# gleis-a-2.net
KiCad netlist of a schematic drawn in EAGLE
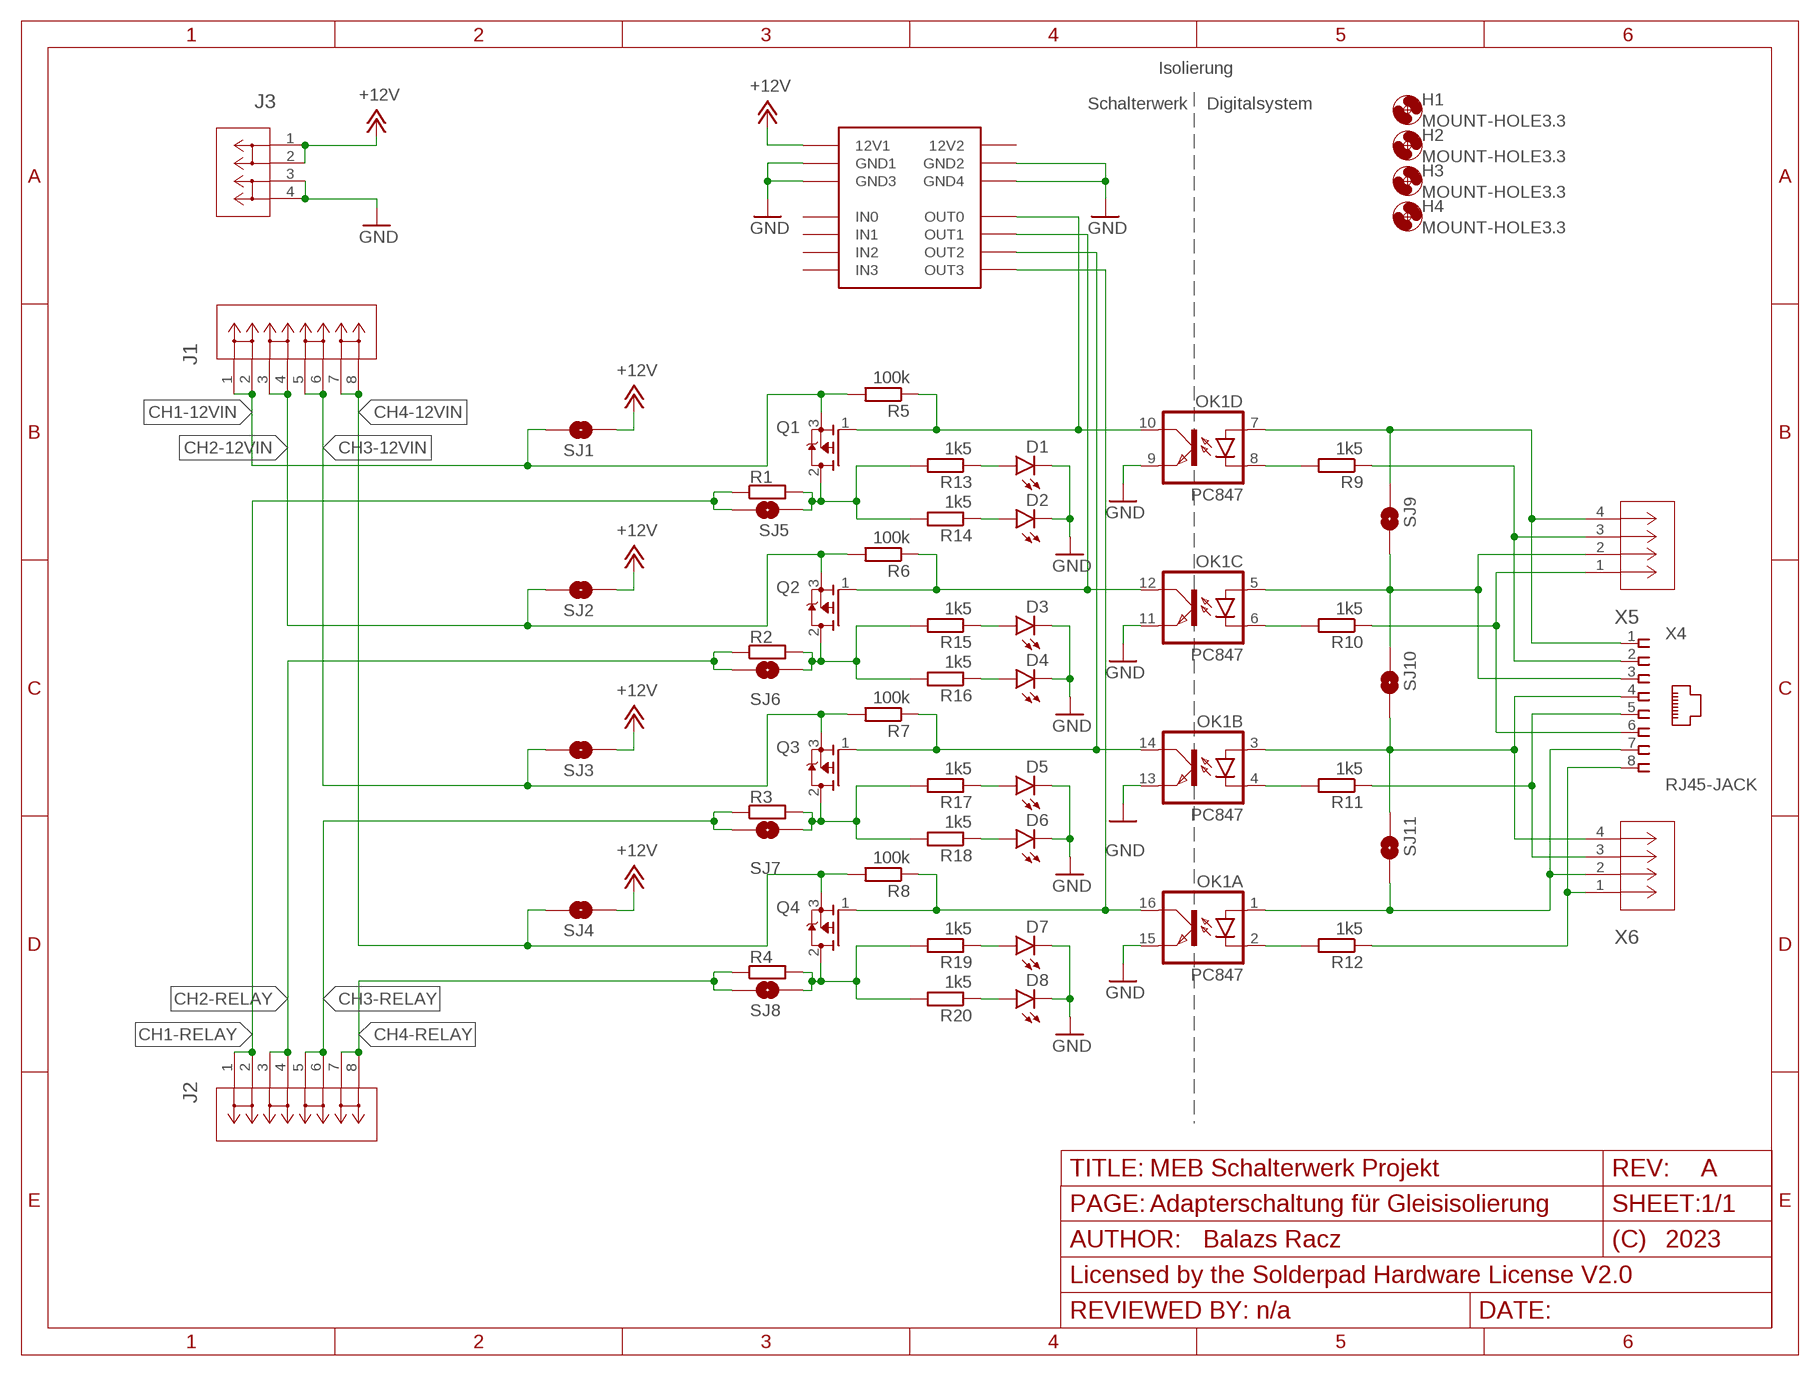
[diagram p0: schematic, sheet 1]

(export (version "E")
  (design (tool "Eeschema 10.0.6"))
  (components
    (comp (ref "D1")
      (value "LEDCHIPLED_0603")
      (footprint "eagle-import:CHIPLED_0603")
      (libsource (lib "eagle-import") (part "LEDCHIPLED_0603"))
    )
    (comp (ref "D2")
      (value "LEDHEADER")
      (footprint "eagle-import:LEDHEADER")
      (libsource (lib "eagle-import") (part "LEDHEADER"))
    )
    (comp (ref "D3")
      (value "LEDCHIPLED_0603")
      (footprint "eagle-import:CHIPLED_0603")
      (libsource (lib "eagle-import") (part "LEDCHIPLED_0603"))
    )
    (comp (ref "D4")
      (value "LEDHEADER")
      (footprint "eagle-import:LEDHEADER")
      (libsource (lib "eagle-import") (part "LEDHEADER"))
    )
    (comp (ref "D5")
      (value "LEDCHIPLED_0603")
      (footprint "eagle-import:CHIPLED_0603")
      (libsource (lib "eagle-import") (part "LEDCHIPLED_0603"))
    )
    (comp (ref "D6")
      (value "LEDHEADER")
      (footprint "eagle-import:LEDHEADER")
      (libsource (lib "eagle-import") (part "LEDHEADER"))
    )
    (comp (ref "D7")
      (value "LEDCHIPLED_0603")
      (footprint "eagle-import:CHIPLED_0603")
      (libsource (lib "eagle-import") (part "LEDCHIPLED_0603"))
    )
    (comp (ref "D8")
      (value "LEDHEADER")
      (footprint "eagle-import:LEDHEADER")
      (libsource (lib "eagle-import") (part "LEDHEADER"))
    )
    (comp (ref "H1")
      (value "MOUNT-HOLE3.3")
      (footprint "eagle-import:3,3")
      (libsource (lib "eagle-import") (part "MOUNT-HOLE3.3"))
    )
    (comp (ref "H2")
      (value "MOUNT-HOLE3.3")
      (footprint "eagle-import:3,3")
      (libsource (lib "eagle-import") (part "MOUNT-HOLE3.3"))
    )
    (comp (ref "H3")
      (value "MOUNT-HOLE3.3")
      (footprint "eagle-import:3,3")
      (libsource (lib "eagle-import") (part "MOUNT-HOLE3.3"))
    )
    (comp (ref "H4")
      (value "MOUNT-HOLE3.3")
      (footprint "eagle-import:3,3")
      (libsource (lib "eagle-import") (part "MOUNT-HOLE3.3"))
    )
    (comp (ref "J1")
      (value "PHNX_4P_508CONN_1017493")
      (footprint "eagle-import:PHNX_4P_508")
      (fields
        (field (name "MANUFACTURER_PART_NUMBER") "1017505")
        (field (name "COPYRIGHT") "Copyright (C) 2023 Ultra Librarian. All rights reserved.")
      )
      (libsource (lib "eagle-import") (part "PHNX_4P_508CONN_1017493"))
    )
    (comp (ref "J2")
      (value "PHNX_4P_508CONN_1017493")
      (footprint "eagle-import:PHNX_4P_508")
      (fields
        (field (name "MANUFACTURER_PART_NUMBER") "1017505")
        (field (name "COPYRIGHT") "Copyright (C) 2023 Ultra Librarian. All rights reserved.")
      )
      (libsource (lib "eagle-import") (part "PHNX_4P_508CONN_1017493"))
    )
    (comp (ref "J3")
      (value "PHNX_2P_508CONN_1017491")
      (footprint "eagle-import:PHNX_2P_508")
      (fields
        (field (name "MANUFACTURER_PART_NUMBER") "1017503")
        (field (name "COPYRIGHT") "Copyright (C) 2023 Ultra Librarian. All rights reserved.")
      )
      (libsource (lib "eagle-import") (part "PHNX_2P_508CONN_1017491"))
    )
    (comp (ref "OK1")
      (value "PC847")
      (footprint "eagle-import:DIL16")
      (libsource (lib "eagle-import") (part "PC847"))
    )
    (comp (ref "Q1")
      (value "P-MOSFET")
      (footprint "eagle-import:DPAK-2")
      (fields (field (name "MANUFACTURER") "Infineon"))
      (libsource (lib "eagle-import") (part "P-MOSFET"))
    )
    (comp (ref "Q2")
      (value "P-MOSFET")
      (footprint "eagle-import:DPAK-2")
      (fields (field (name "MANUFACTURER") "Infineon"))
      (libsource (lib "eagle-import") (part "P-MOSFET"))
    )
    (comp (ref "Q3")
      (value "P-MOSFET")
      (footprint "eagle-import:DPAK-2")
      (fields (field (name "MANUFACTURER") "Infineon"))
      (libsource (lib "eagle-import") (part "P-MOSFET"))
    )
    (comp (ref "Q4")
      (value "P-MOSFET")
      (footprint "eagle-import:DPAK-2")
      (fields (field (name "MANUFACTURER") "Infineon"))
      (libsource (lib "eagle-import") (part "P-MOSFET"))
    )
    (comp (ref "R1")
      (value "R-EU_VTA52")
      (footprint "eagle-import:VTA52")
      (libsource (lib "eagle-import") (part "R-EU_VTA52"))
    )
    (comp (ref "R2")
      (value "R-EU_VTA52")
      (footprint "eagle-import:VTA52")
      (libsource (lib "eagle-import") (part "R-EU_VTA52"))
    )
    (comp (ref "R3")
      (value "R-EU_VTA52")
      (footprint "eagle-import:VTA52")
      (libsource (lib "eagle-import") (part "R-EU_VTA52"))
    )
    (comp (ref "R4")
      (value "R-EU_VTA52")
      (footprint "eagle-import:VTA52")
      (libsource (lib "eagle-import") (part "R-EU_VTA52"))
    )
    (comp (ref "R5")
      (value "100k")
      (footprint "eagle-import:R0805")
      (libsource (lib "eagle-import") (part "R-EU_R0805"))
    )
    (comp (ref "R6")
      (value "100k")
      (footprint "eagle-import:R0805")
      (libsource (lib "eagle-import") (part "R-EU_R0805"))
    )
    (comp (ref "R7")
      (value "100k")
      (footprint "eagle-import:R0805")
      (libsource (lib "eagle-import") (part "R-EU_R0805"))
    )
    (comp (ref "R8")
      (value "100k")
      (footprint "eagle-import:R0805")
      (libsource (lib "eagle-import") (part "R-EU_R0805"))
    )
    (comp (ref "R9")
      (value "1k5")
      (footprint "eagle-import:R0805")
      (libsource (lib "eagle-import") (part "R-EU_R0805"))
    )
    (comp (ref "R10")
      (value "1k5")
      (footprint "eagle-import:R0805")
      (libsource (lib "eagle-import") (part "R-EU_R0805"))
    )
    (comp (ref "R11")
      (value "1k5")
      (footprint "eagle-import:R0805")
      (libsource (lib "eagle-import") (part "R-EU_R0805"))
    )
    (comp (ref "R12")
      (value "1k5")
      (footprint "eagle-import:R0805")
      (libsource (lib "eagle-import") (part "R-EU_R0805"))
    )
    (comp (ref "R13")
      (value "1k5")
      (footprint "eagle-import:R0805")
      (libsource (lib "eagle-import") (part "R-EU_R0805"))
    )
    (comp (ref "R14")
      (value "1k5")
      (footprint "eagle-import:R0805")
      (libsource (lib "eagle-import") (part "R-EU_R0805"))
    )
    (comp (ref "R15")
      (value "1k5")
      (footprint "eagle-import:R0805")
      (libsource (lib "eagle-import") (part "R-EU_R0805"))
    )
    (comp (ref "R16")
      (value "1k5")
      (footprint "eagle-import:R0805")
      (libsource (lib "eagle-import") (part "R-EU_R0805"))
    )
    (comp (ref "R17")
      (value "1k5")
      (footprint "eagle-import:R0805")
      (libsource (lib "eagle-import") (part "R-EU_R0805"))
    )
    (comp (ref "R18")
      (value "1k5")
      (footprint "eagle-import:R0805")
      (libsource (lib "eagle-import") (part "R-EU_R0805"))
    )
    (comp (ref "R19")
      (value "1k5")
      (footprint "eagle-import:R0805")
      (libsource (lib "eagle-import") (part "R-EU_R0805"))
    )
    (comp (ref "R20")
      (value "1k5")
      (footprint "eagle-import:R0805")
      (libsource (lib "eagle-import") (part "R-EU_R0805"))
    )
    (comp (ref "SJ1")
      (value "SJRND2")
      (footprint "eagle-import:SJ_RND2")
      (libsource (lib "eagle-import") (part "SJRND2"))
    )
    (comp (ref "SJ2")
      (value "SJRND2")
      (footprint "eagle-import:SJ_RND2")
      (libsource (lib "eagle-import") (part "SJRND2"))
    )
    (comp (ref "SJ3")
      (value "SJRND2")
      (footprint "eagle-import:SJ_RND2")
      (libsource (lib "eagle-import") (part "SJRND2"))
    )
    (comp (ref "SJ4")
      (value "SJRND2")
      (footprint "eagle-import:SJ_RND2")
      (libsource (lib "eagle-import") (part "SJRND2"))
    )
    (comp (ref "SJ5")
      (value "SJRND2")
      (footprint "eagle-import:SJ_RND2")
      (libsource (lib "eagle-import") (part "SJRND2"))
    )
    (comp (ref "SJ6")
      (value "SJRND2")
      (footprint "eagle-import:SJ_RND2")
      (libsource (lib "eagle-import") (part "SJRND2"))
    )
    (comp (ref "SJ7")
      (value "SJRND2")
      (footprint "eagle-import:SJ_RND2")
      (libsource (lib "eagle-import") (part "SJRND2"))
    )
    (comp (ref "SJ8")
      (value "SJRND2")
      (footprint "eagle-import:SJ_RND2")
      (libsource (lib "eagle-import") (part "SJRND2"))
    )
    (comp (ref "SJ9")
      (value "SJRND2")
      (footprint "eagle-import:SJ_RND2")
      (libsource (lib "eagle-import") (part "SJRND2"))
    )
    (comp (ref "SJ10")
      (value "SJRND2")
      (footprint "eagle-import:SJ_RND2")
      (libsource (lib "eagle-import") (part "SJRND2"))
    )
    (comp (ref "SJ11")
      (value "SJRND2")
      (footprint "eagle-import:SJ_RND2")
      (libsource (lib "eagle-import") (part "SJRND2"))
    )
    (comp (ref "X2")
      (value "IO-HAT")
      (footprint "eagle-import:IOBOARD")
      (libsource (lib "eagle-import") (part "IO-HAT"))
    )
    (comp (ref "X4")
      (value "RJ45-JACK")
      (footprint "eagle-import:RJ45-PULSE-E5J88")
      (libsource (lib "eagle-import") (part "RJ45-JACKRJ45-PULSE-E5J00"))
    )
    (comp (ref "X5")
      (value "PHNX_4P_350CONN_1984989_PXC")
      (footprint "eagle-import:PHNX_4P_350")
      (fields
        (field (name "MANUFACTURER_PART_NUMBER") "1984989")
        (field (name "COPYRIGHT") "Copyright (C) 2023 Ultra Librarian. All rights reserved.")
      )
      (libsource (lib "eagle-import") (part "PHNX_4P_350CONN_1984989_PXC"))
    )
    (comp (ref "X6")
      (value "PHNX_4P_350CONN_1984989_PXC")
      (footprint "eagle-import:PHNX_4P_350")
      (fields
        (field (name "MANUFACTURER_PART_NUMBER") "1984989")
        (field (name "COPYRIGHT") "Copyright (C) 2023 Ultra Librarian. All rights reserved.")
      )
      (libsource (lib "eagle-import") (part "PHNX_4P_350CONN_1984989_PXC"))
    )
  )
  (nets
    (net (code "1") (name "+12V") (class "Default")
      (node (ref "J3") (pin "1") (pinfunction "1_1") (pintype "passive"))
      (node (ref "J3") (pin "2") (pinfunction "2_2") (pintype "passive"))
      (node (ref "SJ1") (pin "P$2") (pinfunction "2_P$2") (pintype "passive"))
      (node (ref "SJ2") (pin "P$2") (pinfunction "2_P$2") (pintype "passive"))
      (node (ref "SJ3") (pin "P$2") (pinfunction "2_P$2") (pintype "passive"))
      (node (ref "SJ4") (pin "P$2") (pinfunction "2_P$2") (pintype "passive"))
      (node (ref "X2") (pin "P$1") (pinfunction "12V1_P$1") (pintype "power_in"))
    )
    (net (code "2") (name "/12V2") (class "Default")
      (node (ref "X2") (pin "P$22") (pinfunction "12V2_P$22") (pintype "power_in"))
    )
    (net (code "3") (name "CH1-12VIN") (class "Default")
      (node (ref "J1") (pin "1") (pinfunction "1_1") (pintype "passive"))
      (node (ref "J1") (pin "2") (pinfunction "2_2") (pintype "passive"))
      (node (ref "Q1") (pin "3") (pinfunction "S_3") (pintype "passive"))
      (node (ref "R5") (pin "2") (pinfunction "2_2") (pintype "passive"))
      (node (ref "SJ1") (pin "P$1") (pinfunction "1_P$1") (pintype "passive"))
    )
    (net (code "4") (name "CH1-RELAY") (class "Default")
      (node (ref "J2") (pin "1") (pinfunction "1_1") (pintype "passive"))
      (node (ref "J2") (pin "2") (pinfunction "2_2") (pintype "passive"))
      (node (ref "R1") (pin "1") (pinfunction "1_1") (pintype "passive"))
      (node (ref "SJ5") (pin "P$1") (pinfunction "1_P$1") (pintype "passive"))
    )
    (net (code "5") (name "CH2-12VIN") (class "Default")
      (node (ref "J1") (pin "3") (pinfunction "3_3") (pintype "passive"))
      (node (ref "J1") (pin "4") (pinfunction "4_4") (pintype "passive"))
      (node (ref "Q2") (pin "3") (pinfunction "S_3") (pintype "passive"))
      (node (ref "R6") (pin "2") (pinfunction "2_2") (pintype "passive"))
      (node (ref "SJ2") (pin "P$1") (pinfunction "1_P$1") (pintype "passive"))
    )
    (net (code "6") (name "CH2-RELAY") (class "Default")
      (node (ref "J2") (pin "3") (pinfunction "3_3") (pintype "passive"))
      (node (ref "J2") (pin "4") (pinfunction "4_4") (pintype "passive"))
      (node (ref "R2") (pin "1") (pinfunction "1_1") (pintype "passive"))
      (node (ref "SJ6") (pin "P$1") (pinfunction "1_P$1") (pintype "passive"))
    )
    (net (code "7") (name "CH3-12VIN") (class "Default")
      (node (ref "J1") (pin "5") (pinfunction "5_5") (pintype "passive"))
      (node (ref "J1") (pin "6") (pinfunction "6_6") (pintype "passive"))
      (node (ref "Q3") (pin "3") (pinfunction "S_3") (pintype "passive"))
      (node (ref "R7") (pin "2") (pinfunction "2_2") (pintype "passive"))
      (node (ref "SJ3") (pin "P$1") (pinfunction "1_P$1") (pintype "passive"))
    )
    (net (code "8") (name "CH3-RELAY") (class "Default")
      (node (ref "J2") (pin "5") (pinfunction "5_5") (pintype "passive"))
      (node (ref "J2") (pin "6") (pinfunction "6_6") (pintype "passive"))
      (node (ref "R3") (pin "1") (pinfunction "1_1") (pintype "passive"))
      (node (ref "SJ7") (pin "P$1") (pinfunction "1_P$1") (pintype "passive"))
    )
    (net (code "9") (name "CH4-12VIN") (class "Default")
      (node (ref "J1") (pin "7") (pinfunction "7_7") (pintype "passive"))
      (node (ref "J1") (pin "8") (pinfunction "8_8") (pintype "passive"))
      (node (ref "Q4") (pin "3") (pinfunction "S_3") (pintype "passive"))
      (node (ref "R8") (pin "2") (pinfunction "2_2") (pintype "passive"))
      (node (ref "SJ4") (pin "P$1") (pinfunction "1_P$1") (pintype "passive"))
    )
    (net (code "10") (name "CH4-RELAY") (class "Default")
      (node (ref "J2") (pin "7") (pinfunction "7_7") (pintype "passive"))
      (node (ref "J2") (pin "8") (pinfunction "8_8") (pintype "passive"))
      (node (ref "R4") (pin "1") (pinfunction "1_1") (pintype "passive"))
      (node (ref "SJ8") (pin "P$1") (pinfunction "1_P$1") (pintype "passive"))
    )
    (net (code "11") (name "GND") (class "Default")
      (node (ref "D1") (pin "C") (pinfunction "C_C") (pintype "passive"))
      (node (ref "D2") (pin "C") (pinfunction "C_C") (pintype "passive"))
      (node (ref "D3") (pin "C") (pinfunction "C_C") (pintype "passive"))
      (node (ref "D4") (pin "C") (pinfunction "C_C") (pintype "passive"))
      (node (ref "D5") (pin "C") (pinfunction "C_C") (pintype "passive"))
      (node (ref "D6") (pin "C") (pinfunction "C_C") (pintype "passive"))
      (node (ref "D7") (pin "C") (pinfunction "C_C") (pintype "passive"))
      (node (ref "D8") (pin "C") (pinfunction "C_C") (pintype "passive"))
      (node (ref "J3") (pin "3") (pinfunction "3_3") (pintype "passive"))
      (node (ref "J3") (pin "4") (pinfunction "4_4") (pintype "passive"))
      (node (ref "OK1") (pin "11") (pinfunction "EMIT_11") (pintype "passive"))
      (node (ref "OK1") (pin "13") (pinfunction "EMIT_13") (pintype "passive"))
      (node (ref "OK1") (pin "15") (pinfunction "EMIT_15") (pintype "passive"))
      (node (ref "OK1") (pin "9") (pinfunction "EMIT_9") (pintype "passive"))
      (node (ref "X2") (pin "P$11") (pinfunction "GND3_P$11") (pintype "power_in"))
      (node (ref "X2") (pin "P$12") (pinfunction "GND4_P$12") (pintype "power_in"))
      (node (ref "X2") (pin "P$2") (pinfunction "GND1_P$2") (pintype "power_in"))
      (node (ref "X2") (pin "P$21") (pinfunction "GND2_P$21") (pintype "power_in"))
    )
    (net (code "12") (name "Net-(D1-PadA)") (class "Default")
      (node (ref "D1") (pin "A") (pinfunction "A_A") (pintype "passive"))
      (node (ref "R13") (pin "1") (pinfunction "1_1") (pintype "passive"))
    )
    (net (code "13") (name "Net-(D2-PadA)") (class "Default")
      (node (ref "D2") (pin "A") (pinfunction "A_A") (pintype "passive"))
      (node (ref "R14") (pin "1") (pinfunction "1_1") (pintype "passive"))
    )
    (net (code "14") (name "Net-(D3-PadA)") (class "Default")
      (node (ref "D3") (pin "A") (pinfunction "A_A") (pintype "passive"))
      (node (ref "R15") (pin "1") (pinfunction "1_1") (pintype "passive"))
    )
    (net (code "15") (name "Net-(D4-PadA)") (class "Default")
      (node (ref "D4") (pin "A") (pinfunction "A_A") (pintype "passive"))
      (node (ref "R16") (pin "1") (pinfunction "1_1") (pintype "passive"))
    )
    (net (code "16") (name "Net-(D5-PadA)") (class "Default")
      (node (ref "D5") (pin "A") (pinfunction "A_A") (pintype "passive"))
      (node (ref "R17") (pin "1") (pinfunction "1_1") (pintype "passive"))
    )
    (net (code "17") (name "Net-(D6-PadA)") (class "Default")
      (node (ref "D6") (pin "A") (pinfunction "A_A") (pintype "passive"))
      (node (ref "R18") (pin "1") (pinfunction "1_1") (pintype "passive"))
    )
    (net (code "18") (name "Net-(D7-PadA)") (class "Default")
      (node (ref "D7") (pin "A") (pinfunction "A_A") (pintype "passive"))
      (node (ref "R19") (pin "1") (pinfunction "1_1") (pintype "passive"))
    )
    (net (code "19") (name "Net-(D8-PadA)") (class "Default")
      (node (ref "D8") (pin "A") (pinfunction "A_A") (pintype "passive"))
      (node (ref "R20") (pin "1") (pinfunction "1_1") (pintype "passive"))
    )
    (net (code "20") (name "Net-(OK1A-A)") (class "Default")
      (node (ref "OK1") (pin "1") (pinfunction "A_1") (pintype "passive"))
      (node (ref "SJ11") (pin "P$1") (pinfunction "1_P$1") (pintype "passive"))
      (node (ref "X4") (pin "7") (pinfunction "7_7") (pintype "passive"))
      (node (ref "X6") (pin "2") (pinfunction "2_2") (pintype "passive"))
    )
    (net (code "21") (name "Net-(OK1A-C)") (class "Default")
      (node (ref "OK1") (pin "2") (pinfunction "C_2") (pintype "passive"))
      (node (ref "R12") (pin "2") (pinfunction "2_2") (pintype "passive"))
    )
    (net (code "22") (name "Net-(OK1A-COL)") (class "Default")
      (node (ref "OK1") (pin "16") (pinfunction "COL_16") (pintype "passive"))
      (node (ref "Q4") (pin "1") (pinfunction "G_1") (pintype "passive"))
      (node (ref "R8") (pin "1") (pinfunction "1_1") (pintype "passive"))
      (node (ref "X2") (pin "P$17") (pinfunction "OUT3_P$17") (pintype "open_collector"))
    )
    (net (code "23") (name "Net-(OK1B-A)") (class "Default")
      (node (ref "OK1") (pin "3") (pinfunction "A_3") (pintype "passive"))
      (node (ref "SJ10") (pin "P$1") (pinfunction "1_P$1") (pintype "passive"))
      (node (ref "SJ11") (pin "P$2") (pinfunction "2_P$2") (pintype "passive"))
      (node (ref "X4") (pin "4") (pinfunction "4_4") (pintype "passive"))
      (node (ref "X6") (pin "4") (pinfunction "4_4") (pintype "passive"))
    )
    (net (code "24") (name "Net-(OK1B-C)") (class "Default")
      (node (ref "OK1") (pin "4") (pinfunction "C_4") (pintype "passive"))
      (node (ref "R11") (pin "2") (pinfunction "2_2") (pintype "passive"))
    )
    (net (code "25") (name "Net-(OK1B-COL)") (class "Default")
      (node (ref "OK1") (pin "14") (pinfunction "COL_14") (pintype "passive"))
      (node (ref "Q3") (pin "1") (pinfunction "G_1") (pintype "passive"))
      (node (ref "R7") (pin "1") (pinfunction "1_1") (pintype "passive"))
      (node (ref "X2") (pin "P$18") (pinfunction "OUT2_P$18") (pintype "open_collector"))
    )
    (net (code "26") (name "Net-(OK1C-A)") (class "Default")
      (node (ref "OK1") (pin "5") (pinfunction "A_5") (pintype "passive"))
      (node (ref "SJ10") (pin "P$2") (pinfunction "2_P$2") (pintype "passive"))
      (node (ref "SJ9") (pin "P$1") (pinfunction "1_P$1") (pintype "passive"))
      (node (ref "X4") (pin "3") (pinfunction "3_3") (pintype "passive"))
      (node (ref "X5") (pin "2") (pinfunction "2_2") (pintype "passive"))
    )
    (net (code "27") (name "Net-(OK1C-C)") (class "Default")
      (node (ref "OK1") (pin "6") (pinfunction "C_6") (pintype "passive"))
      (node (ref "R10") (pin "2") (pinfunction "2_2") (pintype "passive"))
    )
    (net (code "28") (name "Net-(OK1C-COL)") (class "Default")
      (node (ref "OK1") (pin "12") (pinfunction "COL_12") (pintype "passive"))
      (node (ref "Q2") (pin "1") (pinfunction "G_1") (pintype "passive"))
      (node (ref "R6") (pin "1") (pinfunction "1_1") (pintype "passive"))
      (node (ref "X2") (pin "P$19") (pinfunction "OUT1_P$19") (pintype "open_collector"))
    )
    (net (code "29") (name "Net-(OK1D-A)") (class "Default")
      (node (ref "OK1") (pin "7") (pinfunction "A_7") (pintype "passive"))
      (node (ref "SJ9") (pin "P$2") (pinfunction "2_P$2") (pintype "passive"))
      (node (ref "X4") (pin "1") (pinfunction "1_1") (pintype "passive"))
      (node (ref "X5") (pin "4") (pinfunction "4_4") (pintype "passive"))
    )
    (net (code "30") (name "Net-(OK1D-C)") (class "Default")
      (node (ref "OK1") (pin "8") (pinfunction "C_8") (pintype "passive"))
      (node (ref "R9") (pin "2") (pinfunction "2_2") (pintype "passive"))
    )
    (net (code "31") (name "Net-(OK1D-COL)") (class "Default")
      (node (ref "OK1") (pin "10") (pinfunction "COL_10") (pintype "passive"))
      (node (ref "Q1") (pin "1") (pinfunction "G_1") (pintype "passive"))
      (node (ref "R5") (pin "1") (pinfunction "1_1") (pintype "passive"))
      (node (ref "X2") (pin "P$20") (pinfunction "OUT0_P$20") (pintype "open_collector"))
    )
    (net (code "32") (name "Net-(Q1-D)") (class "Default")
      (node (ref "Q1") (pin "2") (pinfunction "D_2") (pintype "passive"))
      (node (ref "R1") (pin "2") (pinfunction "2_2") (pintype "passive"))
      (node (ref "R13") (pin "2") (pinfunction "2_2") (pintype "passive"))
      (node (ref "R14") (pin "2") (pinfunction "2_2") (pintype "passive"))
      (node (ref "SJ5") (pin "P$2") (pinfunction "2_P$2") (pintype "passive"))
    )
    (net (code "33") (name "Net-(Q2-D)") (class "Default")
      (node (ref "Q2") (pin "2") (pinfunction "D_2") (pintype "passive"))
      (node (ref "R15") (pin "2") (pinfunction "2_2") (pintype "passive"))
      (node (ref "R16") (pin "2") (pinfunction "2_2") (pintype "passive"))
      (node (ref "R2") (pin "2") (pinfunction "2_2") (pintype "passive"))
      (node (ref "SJ6") (pin "P$2") (pinfunction "2_P$2") (pintype "passive"))
    )
    (net (code "34") (name "Net-(Q3-D)") (class "Default")
      (node (ref "Q3") (pin "2") (pinfunction "D_2") (pintype "passive"))
      (node (ref "R17") (pin "2") (pinfunction "2_2") (pintype "passive"))
      (node (ref "R18") (pin "2") (pinfunction "2_2") (pintype "passive"))
      (node (ref "R3") (pin "2") (pinfunction "2_2") (pintype "passive"))
      (node (ref "SJ7") (pin "P$2") (pinfunction "2_P$2") (pintype "passive"))
    )
    (net (code "35") (name "Net-(Q4-D)") (class "Default")
      (node (ref "Q4") (pin "2") (pinfunction "D_2") (pintype "passive"))
      (node (ref "R19") (pin "2") (pinfunction "2_2") (pintype "passive"))
      (node (ref "R20") (pin "2") (pinfunction "2_2") (pintype "passive"))
      (node (ref "R4") (pin "2") (pinfunction "2_2") (pintype "passive"))
      (node (ref "SJ8") (pin "P$2") (pinfunction "2_P$2") (pintype "passive"))
    )
    (net (code "36") (name "Net-(R9-Pad1)") (class "Default")
      (node (ref "R9") (pin "1") (pinfunction "1_1") (pintype "passive"))
      (node (ref "X4") (pin "2") (pinfunction "2_2") (pintype "passive"))
      (node (ref "X5") (pin "3") (pinfunction "3_3") (pintype "passive"))
    )
    (net (code "37") (name "Net-(R10-Pad1)") (class "Default")
      (node (ref "R10") (pin "1") (pinfunction "1_1") (pintype "passive"))
      (node (ref "X4") (pin "6") (pinfunction "6_6") (pintype "passive"))
      (node (ref "X5") (pin "1") (pinfunction "1_1") (pintype "passive"))
    )
    (net (code "38") (name "Net-(R11-Pad1)") (class "Default")
      (node (ref "R11") (pin "1") (pinfunction "1_1") (pintype "passive"))
      (node (ref "X4") (pin "5") (pinfunction "5_5") (pintype "passive"))
      (node (ref "X6") (pin "3") (pinfunction "3_3") (pintype "passive"))
    )
    (net (code "39") (name "Net-(R12-Pad1)") (class "Default")
      (node (ref "R12") (pin "1") (pinfunction "1_1") (pintype "passive"))
      (node (ref "X4") (pin "8") (pinfunction "8_8") (pintype "passive"))
      (node (ref "X6") (pin "1") (pinfunction "1_1") (pintype "passive"))
    )
    (net (code "40") (name "unconnected-(X2A-IN0-PadP$3)") (class "Default")
      (node (ref "X2") (pin "P$3") (pinfunction "IN0_P$3") (pintype "input"))
    )
    (net (code "41") (name "unconnected-(X2A-IN1-PadP$4)") (class "Default")
      (node (ref "X2") (pin "P$4") (pinfunction "IN1_P$4") (pintype "input"))
    )
    (net (code "42") (name "unconnected-(X2A-IN2-PadP$5)") (class "Default")
      (node (ref "X2") (pin "P$5") (pinfunction "IN2_P$5") (pintype "input"))
    )
    (net (code "43") (name "unconnected-(X2A-IN3-PadP$6)") (class "Default")
      (node (ref "X2") (pin "P$6") (pinfunction "IN3_P$6") (pintype "input"))
    )
  )
)
